# CircuitClockHandLayout.net
KiCad netlist of a schematic drawn in EAGLE
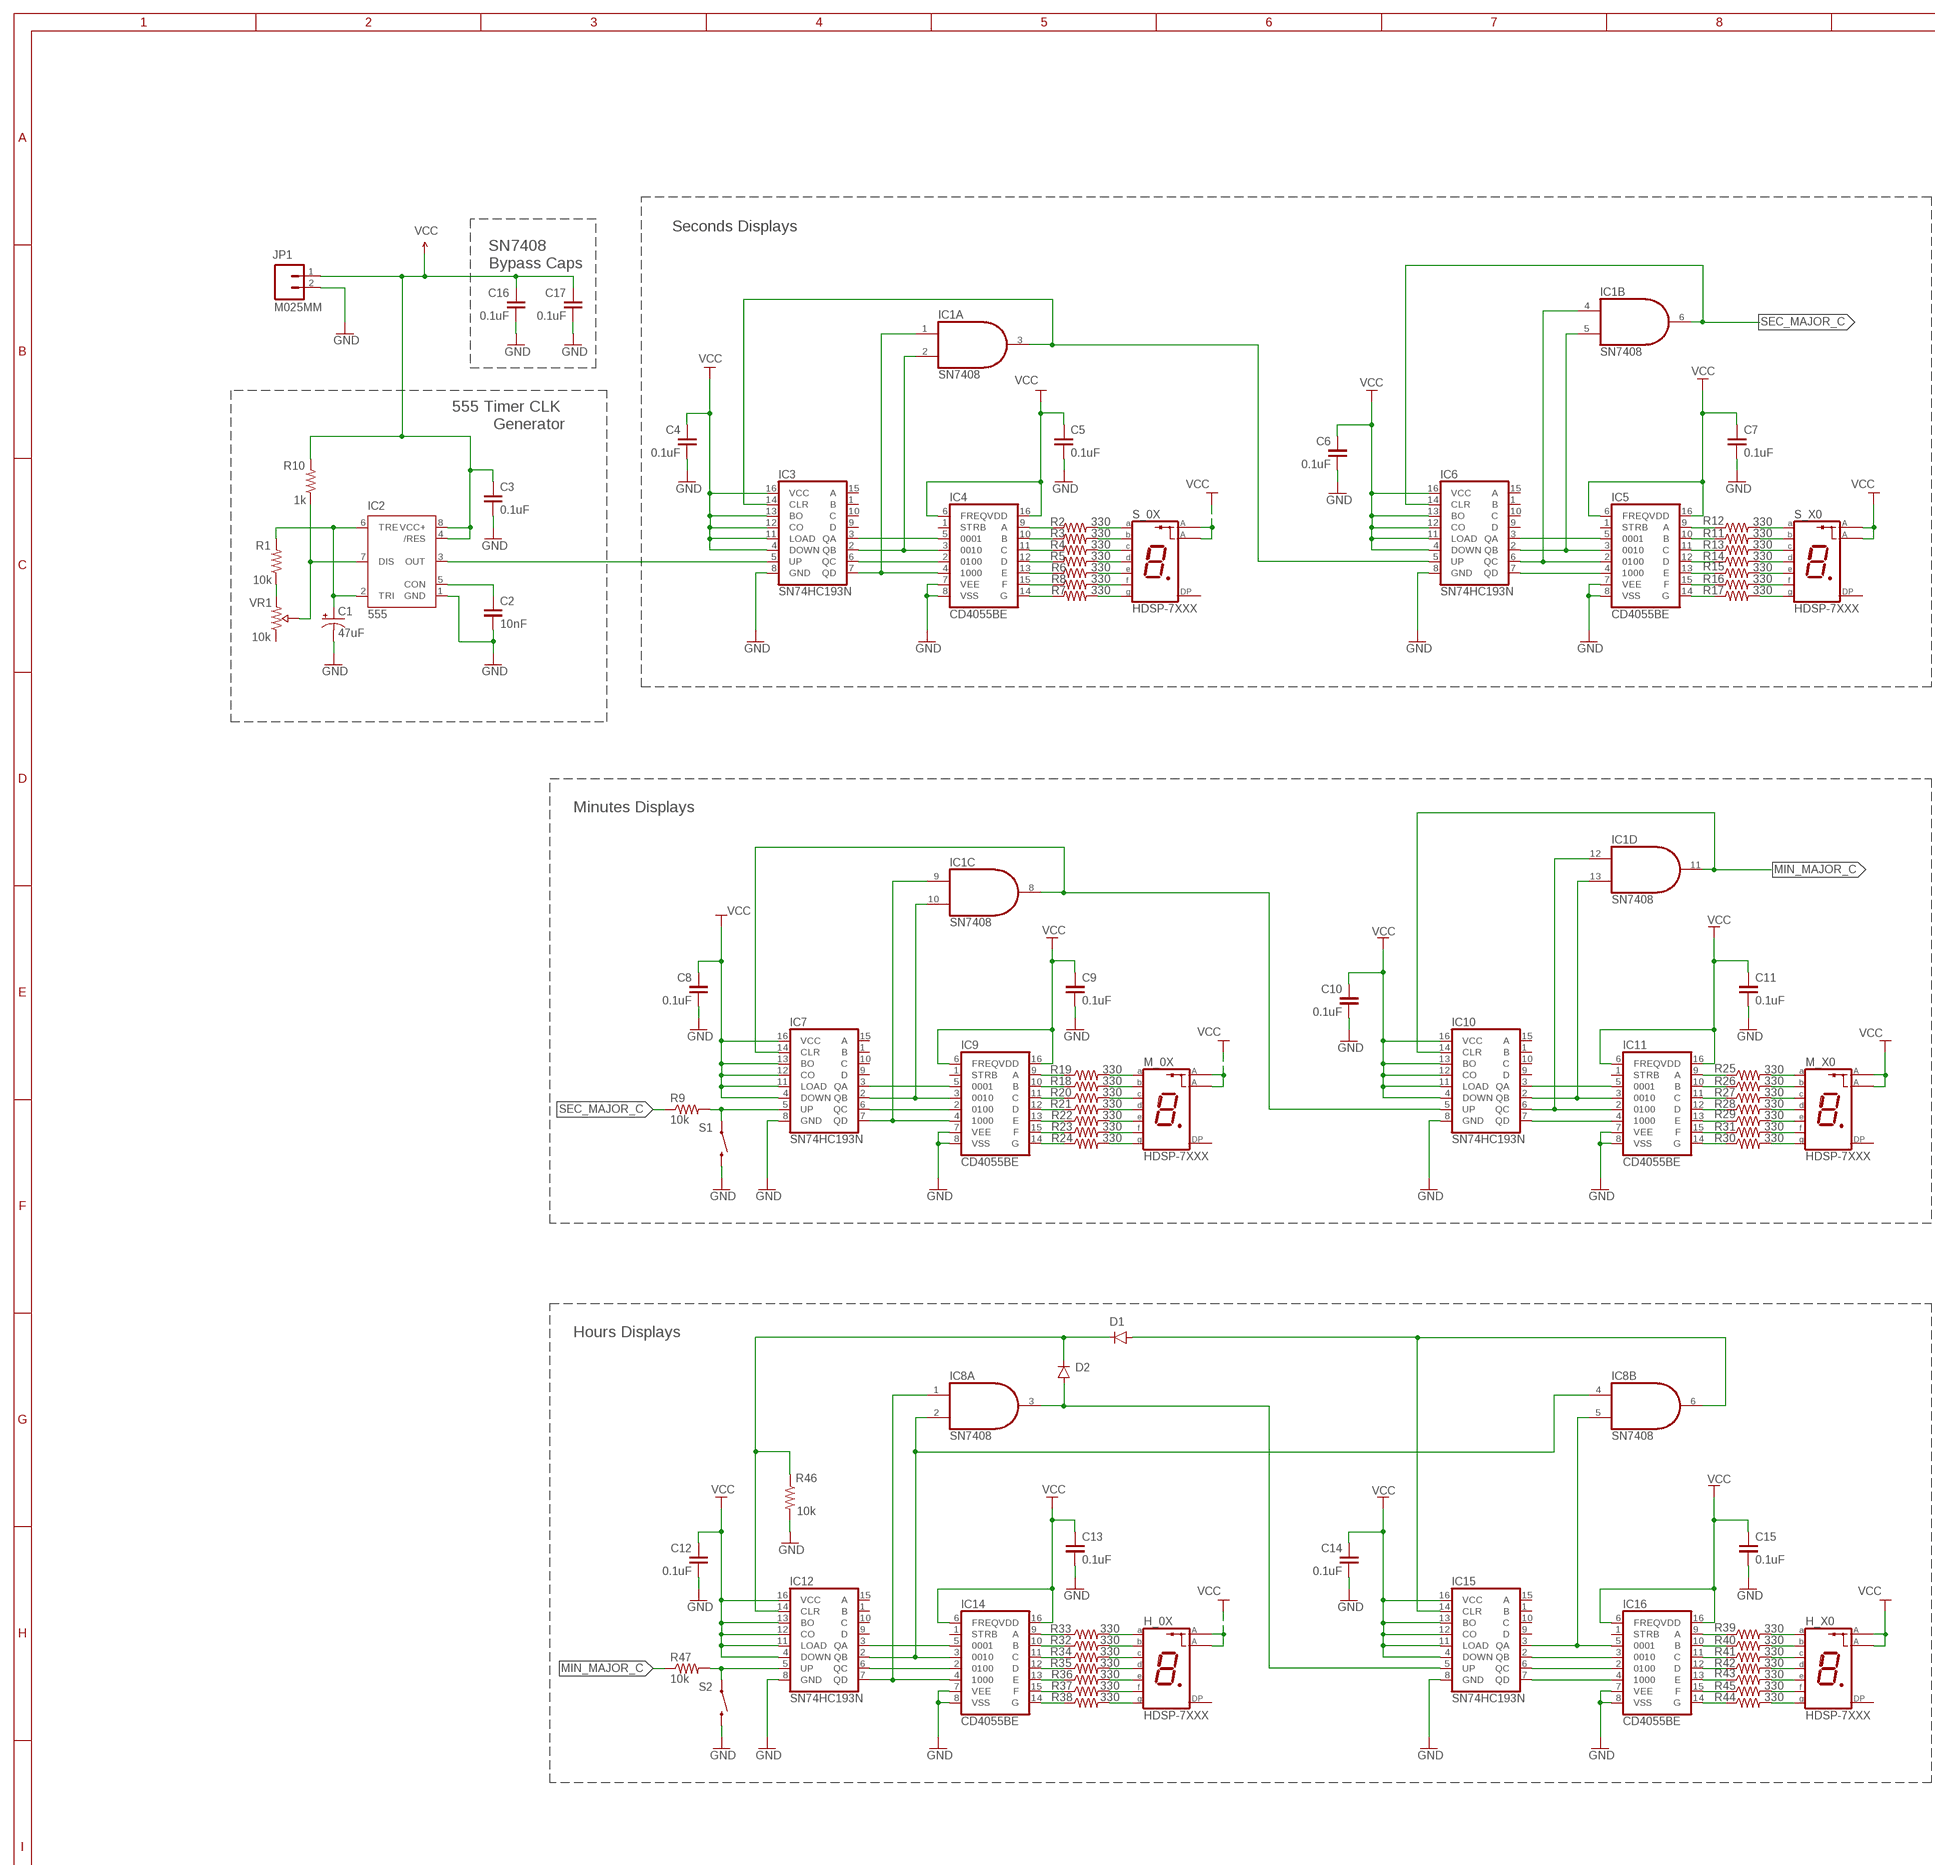
[diagram p0: schematic, sheet 1, part 1 of 2]
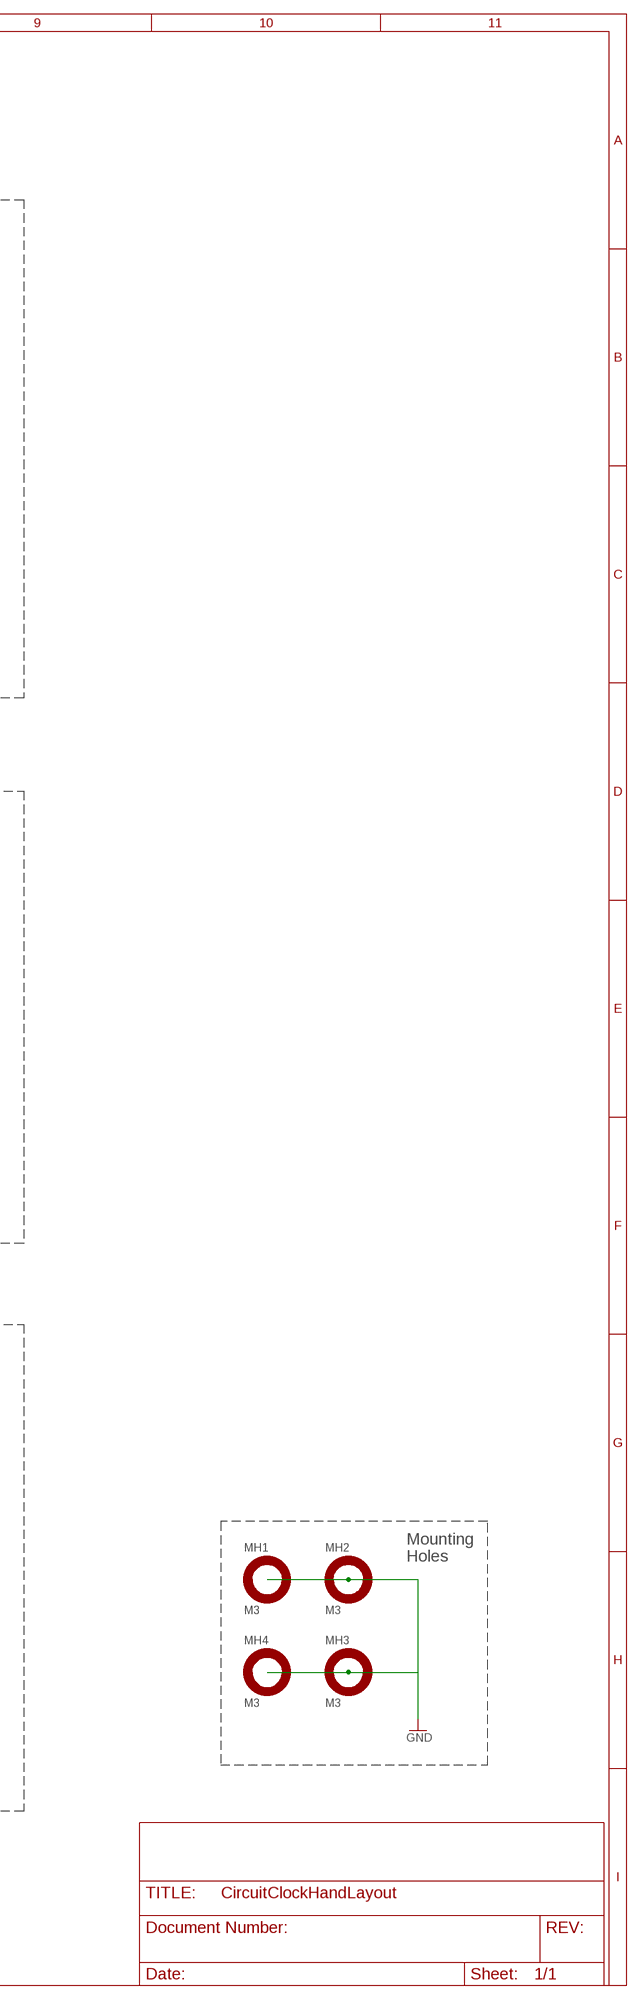
[diagram p1: schematic, sheet 1, part 2 of 2]

(export (version "E")
  (design (tool "Eeschema 10.0.6"))
  (components
    (comp (ref "C1")
      (value "47uF")
      (footprint "eagle-import:2.0MM_LEAD-5.0MM_DIA")
      (libsource (lib "eagle-import") (part "RADIAL_POL2.0MM_LEAD-5.0MM_DIA"))
    )
    (comp (ref "C2")
      (value "10nF")
      (footprint "eagle-import:2.54MM_LEAD")
      (libsource (lib "eagle-import") (part "NON_POL_2.5MM"))
    )
    (comp (ref "C3")
      (value "0.1uF")
      (footprint "eagle-import:2.54MM_LEAD")
      (libsource (lib "eagle-import") (part "NON_POL_2.5MM"))
    )
    (comp (ref "C4")
      (value "0.1uF")
      (footprint "eagle-import:2.54MM_LEAD")
      (libsource (lib "eagle-import") (part "NON_POL_2.5MM"))
    )
    (comp (ref "C5")
      (value "0.1uF")
      (footprint "eagle-import:2.54MM_LEAD")
      (libsource (lib "eagle-import") (part "NON_POL_2.5MM"))
    )
    (comp (ref "C6")
      (value "0.1uF")
      (footprint "eagle-import:2.54MM_LEAD")
      (libsource (lib "eagle-import") (part "NON_POL_2.5MM"))
    )
    (comp (ref "C7")
      (value "0.1uF")
      (footprint "eagle-import:2.54MM_LEAD")
      (libsource (lib "eagle-import") (part "NON_POL_2.5MM"))
    )
    (comp (ref "C8")
      (value "0.1uF")
      (footprint "eagle-import:2.54MM_LEAD")
      (libsource (lib "eagle-import") (part "NON_POL_2.5MM"))
    )
    (comp (ref "C9")
      (value "0.1uF")
      (footprint "eagle-import:2.54MM_LEAD")
      (libsource (lib "eagle-import") (part "NON_POL_2.5MM"))
    )
    (comp (ref "C10")
      (value "0.1uF")
      (footprint "eagle-import:2.54MM_LEAD")
      (libsource (lib "eagle-import") (part "NON_POL_2.5MM"))
    )
    (comp (ref "C11")
      (value "0.1uF")
      (footprint "eagle-import:2.54MM_LEAD")
      (libsource (lib "eagle-import") (part "NON_POL_2.5MM"))
    )
    (comp (ref "C12")
      (value "0.1uF")
      (footprint "eagle-import:2.54MM_LEAD")
      (libsource (lib "eagle-import") (part "NON_POL_2.5MM"))
    )
    (comp (ref "C13")
      (value "0.1uF")
      (footprint "eagle-import:2.54MM_LEAD")
      (libsource (lib "eagle-import") (part "NON_POL_2.5MM"))
    )
    (comp (ref "C14")
      (value "0.1uF")
      (footprint "eagle-import:2.54MM_LEAD")
      (libsource (lib "eagle-import") (part "NON_POL_2.5MM"))
    )
    (comp (ref "C15")
      (value "0.1uF")
      (footprint "eagle-import:2.54MM_LEAD")
      (libsource (lib "eagle-import") (part "NON_POL_2.5MM"))
    )
    (comp (ref "C16")
      (value "0.1uF")
      (footprint "eagle-import:2.54MM_LEAD")
      (libsource (lib "eagle-import") (part "NON_POL_2.5MM"))
    )
    (comp (ref "C17")
      (value "0.1uF")
      (footprint "eagle-import:2.54MM_LEAD")
      (libsource (lib "eagle-import") (part "NON_POL_2.5MM"))
    )
    (comp (ref "D1")
      (value "THROUGH_HOLE_DO-35")
      (footprint "eagle-import:DO35-10")
      (libsource (lib "eagle-import") (part "THROUGH_HOLE_DO-35"))
    )
    (comp (ref "D2")
      (value "THROUGH_HOLE_DO-35")
      (footprint "eagle-import:DO35-10")
      (libsource (lib "eagle-import") (part "THROUGH_HOLE_DO-35"))
    )
    (comp (ref "H_0X")
      (value "HDSP-7XXX")
      (footprint "eagle-import:HDSP-7XXX")
      (libsource (lib "eagle-import") (part "HDSP-7XXX"))
    )
    (comp (ref "H_X0")
      (value "HDSP-7XXX")
      (footprint "eagle-import:HDSP-7XXX")
      (libsource (lib "eagle-import") (part "HDSP-7XXX"))
    )
    (comp (ref "IC1")
      (value "SN7408")
      (footprint "eagle-import:DIL14")
      (libsource (lib "eagle-import") (part "7408NS"))
    )
    (comp (ref "IC2")
      (value "555")
      (footprint "eagle-import:DIP08-KIT")
      (libsource (lib "eagle-import") (part "555KIT"))
    )
    (comp (ref "IC3")
      (value "SN74HC193N")
      (footprint "eagle-import:DIL16")
      (libsource (lib "eagle-import") (part "SN74HC193N"))
    )
    (comp (ref "IC4")
      (value "CD4055BE")
      (footprint "eagle-import:DIL16")
      (libsource (lib "eagle-import") (part "CD4055BE"))
    )
    (comp (ref "IC5")
      (value "CD4055BE")
      (footprint "eagle-import:DIL16")
      (libsource (lib "eagle-import") (part "CD4055BE"))
    )
    (comp (ref "IC6")
      (value "SN74HC193N")
      (footprint "eagle-import:DIL16")
      (libsource (lib "eagle-import") (part "SN74HC193N"))
    )
    (comp (ref "IC7")
      (value "SN74HC193N")
      (footprint "eagle-import:DIL16")
      (libsource (lib "eagle-import") (part "SN74HC193N"))
    )
    (comp (ref "IC8")
      (value "SN7408")
      (footprint "eagle-import:DIL14")
      (libsource (lib "eagle-import") (part "7408NS"))
    )
    (comp (ref "IC9")
      (value "CD4055BE")
      (footprint "eagle-import:DIL16")
      (libsource (lib "eagle-import") (part "CD4055BE"))
    )
    (comp (ref "IC10")
      (value "SN74HC193N")
      (footprint "eagle-import:DIL16")
      (libsource (lib "eagle-import") (part "SN74HC193N"))
    )
    (comp (ref "IC11")
      (value "CD4055BE")
      (footprint "eagle-import:DIL16")
      (libsource (lib "eagle-import") (part "CD4055BE"))
    )
    (comp (ref "IC12")
      (value "SN74HC193N")
      (footprint "eagle-import:DIL16")
      (libsource (lib "eagle-import") (part "SN74HC193N"))
    )
    (comp (ref "IC14")
      (value "CD4055BE")
      (footprint "eagle-import:DIL16")
      (libsource (lib "eagle-import") (part "CD4055BE"))
    )
    (comp (ref "IC15")
      (value "SN74HC193N")
      (footprint "eagle-import:DIL16")
      (libsource (lib "eagle-import") (part "SN74HC193N"))
    )
    (comp (ref "IC16")
      (value "CD4055BE")
      (footprint "eagle-import:DIL16")
      (libsource (lib "eagle-import") (part "CD4055BE"))
    )
    (comp (ref "JP1")
      (value "M025MM")
      (footprint "eagle-import:SCREWTERMINAL-5MM-2")
      (libsource (lib "eagle-import") (part "M025MM"))
    )
    (comp (ref "MH1")
      (value "M3")
      (footprint "eagle-import:M3")
      (libsource (lib "eagle-import") (part "MOUNT_HOLEM3"))
    )
    (comp (ref "MH2")
      (value "M3")
      (footprint "eagle-import:M3")
      (libsource (lib "eagle-import") (part "MOUNT_HOLEM3"))
    )
    (comp (ref "MH3")
      (value "M3")
      (footprint "eagle-import:M3")
      (libsource (lib "eagle-import") (part "MOUNT_HOLEM3"))
    )
    (comp (ref "MH4")
      (value "M3")
      (footprint "eagle-import:M3")
      (libsource (lib "eagle-import") (part "MOUNT_HOLEM3"))
    )
    (comp (ref "M_0X")
      (value "HDSP-7XXX")
      (footprint "eagle-import:HDSP-7XXX")
      (libsource (lib "eagle-import") (part "HDSP-7XXX"))
    )
    (comp (ref "M_X0")
      (value "HDSP-7XXX")
      (footprint "eagle-import:HDSP-7XXX")
      (libsource (lib "eagle-import") (part "HDSP-7XXX"))
    )
    (comp (ref "R1")
      (value "10k")
      (footprint "eagle-import:1_4W_0.3")
      (libsource (lib "eagle-import") (part "THROUGH_HOLE_1/4W_0.3"))
    )
    (comp (ref "R2")
      (value "330")
      (footprint "eagle-import:1_4W_0.3")
      (libsource (lib "eagle-import") (part "THROUGH_HOLE_1/4W_0.3"))
    )
    (comp (ref "R3")
      (value "330")
      (footprint "eagle-import:1_4W_0.3")
      (libsource (lib "eagle-import") (part "THROUGH_HOLE_1/4W_0.3"))
    )
    (comp (ref "R4")
      (value "330")
      (footprint "eagle-import:1_4W_0.3")
      (libsource (lib "eagle-import") (part "THROUGH_HOLE_1/4W_0.3"))
    )
    (comp (ref "R5")
      (value "330")
      (footprint "eagle-import:1_4W_0.3")
      (libsource (lib "eagle-import") (part "THROUGH_HOLE_1/4W_0.3"))
    )
    (comp (ref "R6")
      (value "330")
      (footprint "eagle-import:1_4W_0.3")
      (libsource (lib "eagle-import") (part "THROUGH_HOLE_1/4W_0.3"))
    )
    (comp (ref "R7")
      (value "330")
      (footprint "eagle-import:1_4W_0.3")
      (libsource (lib "eagle-import") (part "THROUGH_HOLE_1/4W_0.3"))
    )
    (comp (ref "R8")
      (value "330")
      (footprint "eagle-import:1_4W_0.3")
      (libsource (lib "eagle-import") (part "THROUGH_HOLE_1/4W_0.3"))
    )
    (comp (ref "R9")
      (value "10k")
      (footprint "eagle-import:1_4W_0.3")
      (libsource (lib "eagle-import") (part "THROUGH_HOLE_1/4W_0.3"))
    )
    (comp (ref "R10")
      (value "1k")
      (footprint "eagle-import:1_4W_0.3")
      (libsource (lib "eagle-import") (part "THROUGH_HOLE_1/4W_0.3"))
    )
    (comp (ref "R11")
      (value "330")
      (footprint "eagle-import:1_4W_0.3")
      (libsource (lib "eagle-import") (part "THROUGH_HOLE_1/4W_0.3"))
    )
    (comp (ref "R12")
      (value "330")
      (footprint "eagle-import:1_4W_0.3")
      (libsource (lib "eagle-import") (part "THROUGH_HOLE_1/4W_0.3"))
    )
    (comp (ref "R13")
      (value "330")
      (footprint "eagle-import:1_4W_0.3")
      (libsource (lib "eagle-import") (part "THROUGH_HOLE_1/4W_0.3"))
    )
    (comp (ref "R14")
      (value "330")
      (footprint "eagle-import:1_4W_0.3")
      (libsource (lib "eagle-import") (part "THROUGH_HOLE_1/4W_0.3"))
    )
    (comp (ref "R15")
      (value "330")
      (footprint "eagle-import:1_4W_0.3")
      (libsource (lib "eagle-import") (part "THROUGH_HOLE_1/4W_0.3"))
    )
    (comp (ref "R16")
      (value "330")
      (footprint "eagle-import:1_4W_0.3")
      (libsource (lib "eagle-import") (part "THROUGH_HOLE_1/4W_0.3"))
    )
    (comp (ref "R17")
      (value "330")
      (footprint "eagle-import:1_4W_0.3")
      (libsource (lib "eagle-import") (part "THROUGH_HOLE_1/4W_0.3"))
    )
    (comp (ref "R18")
      (value "330")
      (footprint "eagle-import:1_4W_0.3")
      (libsource (lib "eagle-import") (part "THROUGH_HOLE_1/4W_0.3"))
    )
    (comp (ref "R19")
      (value "330")
      (footprint "eagle-import:1_4W_0.3")
      (libsource (lib "eagle-import") (part "THROUGH_HOLE_1/4W_0.3"))
    )
    (comp (ref "R20")
      (value "330")
      (footprint "eagle-import:1_4W_0.3")
      (libsource (lib "eagle-import") (part "THROUGH_HOLE_1/4W_0.3"))
    )
    (comp (ref "R21")
      (value "330")
      (footprint "eagle-import:1_4W_0.3")
      (libsource (lib "eagle-import") (part "THROUGH_HOLE_1/4W_0.3"))
    )
    (comp (ref "R22")
      (value "330")
      (footprint "eagle-import:1_4W_0.3")
      (libsource (lib "eagle-import") (part "THROUGH_HOLE_1/4W_0.3"))
    )
    (comp (ref "R23")
      (value "330")
      (footprint "eagle-import:1_4W_0.3")
      (libsource (lib "eagle-import") (part "THROUGH_HOLE_1/4W_0.3"))
    )
    (comp (ref "R24")
      (value "330")
      (footprint "eagle-import:1_4W_0.3")
      (libsource (lib "eagle-import") (part "THROUGH_HOLE_1/4W_0.3"))
    )
    (comp (ref "R25")
      (value "330")
      (footprint "eagle-import:1_4W_0.3")
      (libsource (lib "eagle-import") (part "THROUGH_HOLE_1/4W_0.3"))
    )
    (comp (ref "R26")
      (value "330")
      (footprint "eagle-import:1_4W_0.3")
      (libsource (lib "eagle-import") (part "THROUGH_HOLE_1/4W_0.3"))
    )
    (comp (ref "R27")
      (value "330")
      (footprint "eagle-import:1_4W_0.3")
      (libsource (lib "eagle-import") (part "THROUGH_HOLE_1/4W_0.3"))
    )
    (comp (ref "R28")
      (value "330")
      (footprint "eagle-import:1_4W_0.3")
      (libsource (lib "eagle-import") (part "THROUGH_HOLE_1/4W_0.3"))
    )
    (comp (ref "R29")
      (value "330")
      (footprint "eagle-import:1_4W_0.3")
      (libsource (lib "eagle-import") (part "THROUGH_HOLE_1/4W_0.3"))
    )
    (comp (ref "R30")
      (value "330")
      (footprint "eagle-import:1_4W_0.3")
      (libsource (lib "eagle-import") (part "THROUGH_HOLE_1/4W_0.3"))
    )
    (comp (ref "R31")
      (value "330")
      (footprint "eagle-import:1_4W_0.3")
      (libsource (lib "eagle-import") (part "THROUGH_HOLE_1/4W_0.3"))
    )
    (comp (ref "R32")
      (value "330")
      (footprint "eagle-import:1_4W_0.3")
      (libsource (lib "eagle-import") (part "THROUGH_HOLE_1/4W_0.3"))
    )
    (comp (ref "R33")
      (value "330")
      (footprint "eagle-import:1_4W_0.3")
      (libsource (lib "eagle-import") (part "THROUGH_HOLE_1/4W_0.3"))
    )
    (comp (ref "R34")
      (value "330")
      (footprint "eagle-import:1_4W_0.3")
      (libsource (lib "eagle-import") (part "THROUGH_HOLE_1/4W_0.3"))
    )
    (comp (ref "R35")
      (value "330")
      (footprint "eagle-import:1_4W_0.3")
      (libsource (lib "eagle-import") (part "THROUGH_HOLE_1/4W_0.3"))
    )
    (comp (ref "R36")
      (value "330")
      (footprint "eagle-import:1_4W_0.3")
      (libsource (lib "eagle-import") (part "THROUGH_HOLE_1/4W_0.3"))
    )
    (comp (ref "R37")
      (value "330")
      (footprint "eagle-import:1_4W_0.3")
      (libsource (lib "eagle-import") (part "THROUGH_HOLE_1/4W_0.3"))
    )
    (comp (ref "R38")
      (value "330")
      (footprint "eagle-import:1_4W_0.3")
      (libsource (lib "eagle-import") (part "THROUGH_HOLE_1/4W_0.3"))
    )
    (comp (ref "R39")
      (value "330")
      (footprint "eagle-import:1_4W_0.3")
      (libsource (lib "eagle-import") (part "THROUGH_HOLE_1/4W_0.3"))
    )
    (comp (ref "R40")
      (value "330")
      (footprint "eagle-import:1_4W_0.3")
      (libsource (lib "eagle-import") (part "THROUGH_HOLE_1/4W_0.3"))
    )
    (comp (ref "R41")
      (value "330")
      (footprint "eagle-import:1_4W_0.3")
      (libsource (lib "eagle-import") (part "THROUGH_HOLE_1/4W_0.3"))
    )
    (comp (ref "R42")
      (value "330")
      (footprint "eagle-import:1_4W_0.3")
      (libsource (lib "eagle-import") (part "THROUGH_HOLE_1/4W_0.3"))
    )
    (comp (ref "R43")
      (value "330")
      (footprint "eagle-import:1_4W_0.3")
      (libsource (lib "eagle-import") (part "THROUGH_HOLE_1/4W_0.3"))
    )
    (comp (ref "R44")
      (value "330")
      (footprint "eagle-import:1_4W_0.3")
      (libsource (lib "eagle-import") (part "THROUGH_HOLE_1/4W_0.3"))
    )
    (comp (ref "R45")
      (value "330")
      (footprint "eagle-import:1_4W_0.3")
      (libsource (lib "eagle-import") (part "THROUGH_HOLE_1/4W_0.3"))
    )
    (comp (ref "R46")
      (value "10k")
      (footprint "eagle-import:1_4W_0.3")
      (libsource (lib "eagle-import") (part "THROUGH_HOLE_1/4W_0.3"))
    )
    (comp (ref "R47")
      (value "10k")
      (footprint "eagle-import:1_4W_0.3")
      (libsource (lib "eagle-import") (part "THROUGH_HOLE_1/4W_0.3"))
    )
    (comp (ref "S1")
      (value "SWITCH-MOMENTARY-2PTH")
      (footprint "eagle-import:TACTILE-PTH")
      (libsource (lib "eagle-import") (part "SWITCH-MOMENTARY-2PTH"))
    )
    (comp (ref "S2")
      (value "SWITCH-MOMENTARY-2PTH")
      (footprint "eagle-import:TACTILE-PTH")
      (libsource (lib "eagle-import") (part "SWITCH-MOMENTARY-2PTH"))
    )
    (comp (ref "S_0X")
      (value "HDSP-7XXX")
      (footprint "eagle-import:HDSP-7XXX")
      (libsource (lib "eagle-import") (part "HDSP-7XXX"))
    )
    (comp (ref "S_X0")
      (value "HDSP-7XXX")
      (footprint "eagle-import:HDSP-7XXX")
      (libsource (lib "eagle-import") (part "HDSP-7XXX"))
    )
    (comp (ref "VR1")
      (value "10k")
      (footprint "eagle-import:3296")
      (libsource (lib "eagle-import") (part "TRIM_POTS_BOURNS_3296"))
    )
  )
  (nets
    (net (code "1") (name "GND") (class "Default")
      (node (ref "C1") (pin "-") (pinfunction "-_-") (pintype "passive"))
      (node (ref "C10") (pin "2") (pinfunction "2_2") (pintype "passive"))
      (node (ref "C11") (pin "2") (pinfunction "2_2") (pintype "passive"))
      (node (ref "C12") (pin "2") (pinfunction "2_2") (pintype "passive"))
      (node (ref "C13") (pin "2") (pinfunction "2_2") (pintype "passive"))
      (node (ref "C14") (pin "2") (pinfunction "2_2") (pintype "passive"))
      (node (ref "C15") (pin "2") (pinfunction "2_2") (pintype "passive"))
      (node (ref "C16") (pin "2") (pinfunction "2_2") (pintype "passive"))
      (node (ref "C17") (pin "2") (pinfunction "2_2") (pintype "passive"))
      (node (ref "C2") (pin "2") (pinfunction "2_2") (pintype "passive"))
      (node (ref "C3") (pin "2") (pinfunction "2_2") (pintype "passive"))
      (node (ref "C4") (pin "2") (pinfunction "2_2") (pintype "passive"))
      (node (ref "C5") (pin "2") (pinfunction "2_2") (pintype "passive"))
      (node (ref "C6") (pin "2") (pinfunction "2_2") (pintype "passive"))
      (node (ref "C7") (pin "2") (pinfunction "2_2") (pintype "passive"))
      (node (ref "C8") (pin "2") (pinfunction "2_2") (pintype "passive"))
      (node (ref "C9") (pin "2") (pinfunction "2_2") (pintype "passive"))
      (node (ref "IC10") (pin "8") (pinfunction "GND_8") (pintype "power_in"))
      (node (ref "IC11") (pin "7") (pinfunction "VEE_7") (pintype "bidirectional"))
      (node (ref "IC11") (pin "8") (pinfunction "VSS_8") (pintype "power_in"))
      (node (ref "IC12") (pin "8") (pinfunction "GND_8") (pintype "power_in"))
      (node (ref "IC14") (pin "7") (pinfunction "VEE_7") (pintype "bidirectional"))
      (node (ref "IC14") (pin "8") (pinfunction "VSS_8") (pintype "power_in"))
      (node (ref "IC15") (pin "8") (pinfunction "GND_8") (pintype "power_in"))
      (node (ref "IC16") (pin "7") (pinfunction "VEE_7") (pintype "bidirectional"))
      (node (ref "IC16") (pin "8") (pinfunction "VSS_8") (pintype "power_in"))
      (node (ref "IC2") (pin "1") (pinfunction "GND_1") (pintype "power_in"))
      (node (ref "IC3") (pin "8") (pinfunction "GND_8") (pintype "power_in"))
      (node (ref "IC4") (pin "7") (pinfunction "VEE_7") (pintype "bidirectional"))
      (node (ref "IC4") (pin "8") (pinfunction "VSS_8") (pintype "power_in"))
      (node (ref "IC5") (pin "7") (pinfunction "VEE_7") (pintype "bidirectional"))
      (node (ref "IC5") (pin "8") (pinfunction "VSS_8") (pintype "power_in"))
      (node (ref "IC6") (pin "8") (pinfunction "GND_8") (pintype "power_in"))
      (node (ref "IC7") (pin "8") (pinfunction "GND_8") (pintype "power_in"))
      (node (ref "IC9") (pin "7") (pinfunction "VEE_7") (pintype "bidirectional"))
      (node (ref "IC9") (pin "8") (pinfunction "VSS_8") (pintype "power_in"))
      (node (ref "JP1") (pin "2") (pinfunction "2_2") (pintype "passive"))
      (node (ref "MH1") (pin "P$1") (pinfunction "P$1_P$1") (pintype "bidirectional"))
      (node (ref "MH2") (pin "P$1") (pinfunction "P$1_P$1") (pintype "bidirectional"))
      (node (ref "MH3") (pin "P$1") (pinfunction "P$1_P$1") (pintype "bidirectional"))
      (node (ref "MH4") (pin "P$1") (pinfunction "P$1_P$1") (pintype "bidirectional"))
      (node (ref "R46") (pin "P$2") (pinfunction "2_P$2") (pintype "passive"))
      (node (ref "S1") (pin "3") (pinfunction "2_3") (pintype "passive"))
      (node (ref "S2") (pin "3") (pinfunction "2_3") (pintype "passive"))
    )
    (net (code "2") (name "MIN_MAJOR_C") (class "Default")
      (node (ref "IC1") (pin "11") (pinfunction "O_11") (pintype "output"))
      (node (ref "IC10") (pin "14") (pinfunction "CLR_14") (pintype "bidirectional"))
      (node (ref "R47") (pin "P$1") (pinfunction "1_P$1") (pintype "passive"))
    )
    (net (code "3") (name "Net-(H_0X-B)") (class "Default")
      (node (ref "H_0X") (pin "P$9") (pinfunction "B_P$9") (pintype "passive"))
      (node (ref "R32") (pin "P$2") (pinfunction "2_P$2") (pintype "passive"))
    )
    (net (code "4") (name "Net-(H_0X-C)") (class "Default")
      (node (ref "H_0X") (pin "P$8") (pinfunction "C_P$8") (pintype "passive"))
      (node (ref "R34") (pin "P$2") (pinfunction "2_P$2") (pintype "passive"))
    )
    (net (code "5") (name "Net-(H_0X-D)") (class "Default")
      (node (ref "H_0X") (pin "P$5") (pinfunction "D_P$5") (pintype "passive"))
      (node (ref "R35") (pin "P$2") (pinfunction "2_P$2") (pintype "passive"))
    )
    (net (code "6") (name "Net-(H_0X-E)") (class "Default")
      (node (ref "H_0X") (pin "P$4") (pinfunction "E_P$4") (pintype "passive"))
      (node (ref "R36") (pin "P$2") (pinfunction "2_P$2") (pintype "passive"))
    )
    (net (code "7") (name "Net-(H_0X-F)") (class "Default")
      (node (ref "H_0X") (pin "P$2") (pinfunction "F_P$2") (pintype "passive"))
      (node (ref "R37") (pin "P$2") (pinfunction "2_P$2") (pintype "passive"))
    )
    (net (code "8") (name "Net-(H_0X-G)") (class "Default")
      (node (ref "H_0X") (pin "P$3") (pinfunction "G_P$3") (pintype "passive"))
      (node (ref "R38") (pin "P$2") (pinfunction "2_P$2") (pintype "passive"))
    )
    (net (code "9") (name "Net-(H_X0-B)") (class "Default")
      (node (ref "H_X0") (pin "P$9") (pinfunction "B_P$9") (pintype "passive"))
      (node (ref "R40") (pin "P$2") (pinfunction "2_P$2") (pintype "passive"))
    )
    (net (code "10") (name "Net-(H_X0-C)") (class "Default")
      (node (ref "H_X0") (pin "P$8") (pinfunction "C_P$8") (pintype "passive"))
      (node (ref "R41") (pin "P$2") (pinfunction "2_P$2") (pintype "passive"))
    )
    (net (code "11") (name "Net-(H_X0-D)") (class "Default")
      (node (ref "H_X0") (pin "P$5") (pinfunction "D_P$5") (pintype "passive"))
      (node (ref "R42") (pin "P$2") (pinfunction "2_P$2") (pintype "passive"))
    )
    (net (code "12") (name "Net-(H_X0-E)") (class "Default")
      (node (ref "H_X0") (pin "P$4") (pinfunction "E_P$4") (pintype "passive"))
      (node (ref "R43") (pin "P$2") (pinfunction "2_P$2") (pintype "passive"))
    )
    (net (code "13") (name "Net-(H_X0-F)") (class "Default")
      (node (ref "H_X0") (pin "P$2") (pinfunction "F_P$2") (pintype "passive"))
      (node (ref "R45") (pin "P$2") (pinfunction "2_P$2") (pintype "passive"))
    )
    (net (code "14") (name "Net-(H_X0-G)") (class "Default")
      (node (ref "H_X0") (pin "P$3") (pinfunction "G_P$3") (pintype "passive"))
      (node (ref "R44") (pin "P$2") (pinfunction "2_P$2") (pintype "passive"))
    )
    (net (code "15") (name "Net-(IC1A-I0)") (class "Default")
      (node (ref "IC1") (pin "1") (pinfunction "I0_1") (pintype "input"))
      (node (ref "IC3") (pin "7") (pinfunction "QD_7") (pintype "bidirectional"))
      (node (ref "IC4") (pin "4") (pinfunction "1000_4") (pintype "bidirectional"))
    )
    (net (code "16") (name "Net-(IC1A-I1)") (class "Default")
      (node (ref "IC1") (pin "2") (pinfunction "I1_2") (pintype "input"))
      (node (ref "IC3") (pin "2") (pinfunction "QB_2") (pintype "bidirectional"))
      (node (ref "IC4") (pin "3") (pinfunction "0010_3") (pintype "input"))
    )
    (net (code "17") (name "Net-(IC1A-O)") (class "Default")
      (node (ref "IC1") (pin "3") (pinfunction "O_3") (pintype "output"))
      (node (ref "IC3") (pin "14") (pinfunction "CLR_14") (pintype "bidirectional"))
      (node (ref "IC6") (pin "5") (pinfunction "UP_5") (pintype "bidirectional"))
    )
    (net (code "18") (name "Net-(IC1B-I0)") (class "Default")
      (node (ref "IC1") (pin "4") (pinfunction "I0_4") (pintype "input"))
      (node (ref "IC5") (pin "2") (pinfunction "0100_2") (pintype "input"))
      (node (ref "IC6") (pin "6") (pinfunction "QC_6") (pintype "bidirectional"))
    )
    (net (code "19") (name "Net-(IC1B-I1)") (class "Default")
      (node (ref "IC1") (pin "5") (pinfunction "I1_5") (pintype "input"))
      (node (ref "IC5") (pin "3") (pinfunction "0010_3") (pintype "input"))
      (node (ref "IC6") (pin "2") (pinfunction "QB_2") (pintype "bidirectional"))
    )
    (net (code "20") (name "Net-(IC1C-I0)") (class "Default")
      (node (ref "IC1") (pin "9") (pinfunction "I0_9") (pintype "input"))
      (node (ref "IC7") (pin "7") (pinfunction "QD_7") (pintype "bidirectional"))
      (node (ref "IC9") (pin "4") (pinfunction "1000_4") (pintype "bidirectional"))
    )
    (net (code "21") (name "Net-(IC1C-I1)") (class "Default")
      (node (ref "IC1") (pin "10") (pinfunction "I1_10") (pintype "input"))
      (node (ref "IC7") (pin "2") (pinfunction "QB_2") (pintype "bidirectional"))
      (node (ref "IC9") (pin "3") (pinfunction "0010_3") (pintype "input"))
    )
    (net (code "22") (name "Net-(IC2-CON)") (class "Default")
      (node (ref "C2") (pin "1") (pinfunction "1_1") (pintype "passive"))
      (node (ref "IC2") (pin "5") (pinfunction "CON_5") (pintype "input"))
    )
    (net (code "23") (name "Net-(IC2-DIS)") (class "Default")
      (node (ref "IC2") (pin "7") (pinfunction "DIS_7") (pintype "input"))
      (node (ref "R10") (pin "P$1") (pinfunction "1_P$1") (pintype "passive"))
      (node (ref "VR1") (pin "2") (pinfunction "S_2") (pintype "passive"))
    )
    (net (code "24") (name "Net-(IC2-OUT)") (class "Default")
      (node (ref "IC2") (pin "3") (pinfunction "OUT_3") (pintype "output"))
      (node (ref "IC3") (pin "5") (pinfunction "UP_5") (pintype "bidirectional"))
    )
    (net (code "25") (name "Net-(IC2-TRE)") (class "Default")
      (node (ref "C1") (pin "+") (pinfunction "+_+") (pintype "passive"))
      (node (ref "IC2") (pin "2") (pinfunction "TRI_2") (pintype "input"))
      (node (ref "IC2") (pin "6") (pinfunction "TRE_6") (pintype "input"))
      (node (ref "R1") (pin "P$2") (pinfunction "2_P$2") (pintype "passive"))
    )
    (net (code "26") (name "Net-(IC3-QA)") (class "Default")
      (node (ref "IC3") (pin "3") (pinfunction "QA_3") (pintype "bidirectional"))
      (node (ref "IC4") (pin "5") (pinfunction "0001_5") (pintype "input"))
    )
    (net (code "27") (name "Net-(IC3-QC)") (class "Default")
      (node (ref "IC3") (pin "6") (pinfunction "QC_6") (pintype "bidirectional"))
      (node (ref "IC4") (pin "2") (pinfunction "0100_2") (pintype "input"))
    )
    (net (code "28") (name "Net-(IC4-A)") (class "Default")
      (node (ref "IC4") (pin "9") (pinfunction "A_9") (pintype "bidirectional"))
      (node (ref "R2") (pin "P$1") (pinfunction "1_P$1") (pintype "passive"))
    )
    (net (code "29") (name "Net-(IC4-B)") (class "Default")
      (node (ref "IC4") (pin "10") (pinfunction "B_10") (pintype "bidirectional"))
      (node (ref "R3") (pin "P$1") (pinfunction "1_P$1") (pintype "passive"))
    )
    (net (code "30") (name "Net-(IC4-C)") (class "Default")
      (node (ref "IC4") (pin "11") (pinfunction "C_11") (pintype "bidirectional"))
      (node (ref "R4") (pin "P$1") (pinfunction "1_P$1") (pintype "passive"))
    )
    (net (code "31") (name "Net-(IC4-D)") (class "Default")
      (node (ref "IC4") (pin "12") (pinfunction "D_12") (pintype "bidirectional"))
      (node (ref "R5") (pin "P$1") (pinfunction "1_P$1") (pintype "passive"))
    )
    (net (code "32") (name "Net-(IC4-E)") (class "Default")
      (node (ref "IC4") (pin "13") (pinfunction "E_13") (pintype "bidirectional"))
      (node (ref "R6") (pin "P$1") (pinfunction "1_P$1") (pintype "passive"))
    )
    (net (code "33") (name "Net-(IC4-F)") (class "Default")
      (node (ref "IC4") (pin "15") (pinfunction "F_15") (pintype "bidirectional"))
      (node (ref "R8") (pin "P$1") (pinfunction "1_P$1") (pintype "passive"))
    )
    (net (code "34") (name "Net-(IC4-G)") (class "Default")
      (node (ref "IC4") (pin "14") (pinfunction "G_14") (pintype "bidirectional"))
      (node (ref "R7") (pin "P$1") (pinfunction "1_P$1") (pintype "passive"))
    )
    (net (code "35") (name "Net-(IC5-0001)") (class "Default")
      (node (ref "IC5") (pin "5") (pinfunction "0001_5") (pintype "input"))
      (node (ref "IC6") (pin "3") (pinfunction "QA_3") (pintype "bidirectional"))
    )
    (net (code "36") (name "Net-(IC5-1000)") (class "Default")
      (node (ref "IC5") (pin "4") (pinfunction "1000_4") (pintype "bidirectional"))
      (node (ref "IC6") (pin "7") (pinfunction "QD_7") (pintype "bidirectional"))
    )
    (net (code "37") (name "Net-(IC5-A)") (class "Default")
      (node (ref "IC5") (pin "9") (pinfunction "A_9") (pintype "bidirectional"))
      (node (ref "R12") (pin "P$1") (pinfunction "1_P$1") (pintype "passive"))
    )
    (net (code "38") (name "Net-(IC5-B)") (class "Default")
      (node (ref "IC5") (pin "10") (pinfunction "B_10") (pintype "bidirectional"))
      (node (ref "R11") (pin "P$1") (pinfunction "1_P$1") (pintype "passive"))
    )
    (net (code "39") (name "Net-(IC5-C)") (class "Default")
      (node (ref "IC5") (pin "11") (pinfunction "C_11") (pintype "bidirectional"))
      (node (ref "R13") (pin "P$1") (pinfunction "1_P$1") (pintype "passive"))
    )
    (net (code "40") (name "Net-(IC5-D)") (class "Default")
      (node (ref "IC5") (pin "12") (pinfunction "D_12") (pintype "bidirectional"))
      (node (ref "R14") (pin "P$1") (pinfunction "1_P$1") (pintype "passive"))
    )
    (net (code "41") (name "Net-(IC5-E)") (class "Default")
      (node (ref "IC5") (pin "13") (pinfunction "E_13") (pintype "bidirectional"))
      (node (ref "R15") (pin "P$1") (pinfunction "1_P$1") (pintype "passive"))
    )
    (net (code "42") (name "Net-(IC5-F)") (class "Default")
      (node (ref "IC5") (pin "15") (pinfunction "F_15") (pintype "bidirectional"))
      (node (ref "R16") (pin "P$1") (pinfunction "1_P$1") (pintype "passive"))
    )
    (net (code "43") (name "Net-(IC5-G)") (class "Default")
      (node (ref "IC5") (pin "14") (pinfunction "G_14") (pintype "bidirectional"))
      (node (ref "R17") (pin "P$1") (pinfunction "1_P$1") (pintype "passive"))
    )
    (net (code "44") (name "Net-(IC7-QA)") (class "Default")
      (node (ref "IC7") (pin "3") (pinfunction "QA_3") (pintype "bidirectional"))
      (node (ref "IC9") (pin "5") (pinfunction "0001_5") (pintype "input"))
    )
    (net (code "45") (name "Net-(IC7-QC)") (class "Default")
      (node (ref "IC7") (pin "6") (pinfunction "QC_6") (pintype "bidirectional"))
      (node (ref "IC9") (pin "2") (pinfunction "0100_2") (pintype "input"))
    )
    (net (code "46") (name "Net-(IC7-UP)") (class "Default")
      (node (ref "IC7") (pin "5") (pinfunction "UP_5") (pintype "bidirectional"))
      (node (ref "R9") (pin "P$2") (pinfunction "2_P$2") (pintype "passive"))
      (node (ref "S1") (pin "1") (pinfunction "1_1") (pintype "passive"))
    )
    (net (code "47") (name "Net-(IC9-A)") (class "Default")
      (node (ref "IC9") (pin "9") (pinfunction "A_9") (pintype "bidirectional"))
      (node (ref "R19") (pin "P$1") (pinfunction "1_P$1") (pintype "passive"))
    )
    (net (code "48") (name "Net-(IC9-B)") (class "Default")
      (node (ref "IC9") (pin "10") (pinfunction "B_10") (pintype "bidirectional"))
      (node (ref "R18") (pin "P$1") (pinfunction "1_P$1") (pintype "passive"))
    )
    (net (code "49") (name "Net-(IC9-C)") (class "Default")
      (node (ref "IC9") (pin "11") (pinfunction "C_11") (pintype "bidirectional"))
      (node (ref "R20") (pin "P$1") (pinfunction "1_P$1") (pintype "passive"))
    )
    (net (code "50") (name "Net-(IC9-D)") (class "Default")
      (node (ref "IC9") (pin "12") (pinfunction "D_12") (pintype "bidirectional"))
      (node (ref "R21") (pin "P$1") (pinfunction "1_P$1") (pintype "passive"))
    )
    (net (code "51") (name "Net-(IC9-E)") (class "Default")
      (node (ref "IC9") (pin "13") (pinfunction "E_13") (pintype "bidirectional"))
      (node (ref "R22") (pin "P$1") (pinfunction "1_P$1") (pintype "passive"))
    )
    (net (code "52") (name "Net-(IC9-F)") (class "Default")
      (node (ref "IC9") (pin "15") (pinfunction "F_15") (pintype "bidirectional"))
      (node (ref "R23") (pin "P$1") (pinfunction "1_P$1") (pintype "passive"))
    )
    (net (code "53") (name "Net-(IC9-G)") (class "Default")
      (node (ref "IC9") (pin "14") (pinfunction "G_14") (pintype "bidirectional"))
      (node (ref "R24") (pin "P$1") (pinfunction "1_P$1") (pintype "passive"))
    )
    (net (code "54") (name "Net-(IC10-QA)") (class "Default")
      (node (ref "IC10") (pin "3") (pinfunction "QA_3") (pintype "bidirectional"))
      (node (ref "IC11") (pin "5") (pinfunction "0001_5") (pintype "input"))
    )
    (net (code "55") (name "Net-(IC10-QB)") (class "Default")
      (node (ref "IC1") (pin "13") (pinfunction "I1_13") (pintype "input"))
      (node (ref "IC10") (pin "2") (pinfunction "QB_2") (pintype "bidirectional"))
      (node (ref "IC11") (pin "3") (pinfunction "0010_3") (pintype "input"))
    )
    (net (code "56") (name "Net-(IC10-QC)") (class "Default")
      (node (ref "IC1") (pin "12") (pinfunction "I0_12") (pintype "input"))
      (node (ref "IC10") (pin "6") (pinfunction "QC_6") (pintype "bidirectional"))
      (node (ref "IC11") (pin "2") (pinfunction "0100_2") (pintype "input"))
    )
    (net (code "57") (name "Net-(IC10-QD)") (class "Default")
      (node (ref "IC10") (pin "7") (pinfunction "QD_7") (pintype "bidirectional"))
      (node (ref "IC11") (pin "4") (pinfunction "1000_4") (pintype "bidirectional"))
    )
    (net (code "58") (name "Net-(IC10-UP)") (class "Default")
      (node (ref "IC1") (pin "8") (pinfunction "O_8") (pintype "output"))
      (node (ref "IC10") (pin "5") (pinfunction "UP_5") (pintype "bidirectional"))
      (node (ref "IC7") (pin "14") (pinfunction "CLR_14") (pintype "bidirectional"))
    )
    (net (code "59") (name "Net-(IC11-A)") (class "Default")
      (node (ref "IC11") (pin "9") (pinfunction "A_9") (pintype "bidirectional"))
      (node (ref "R25") (pin "P$1") (pinfunction "1_P$1") (pintype "passive"))
    )
    (net (code "60") (name "Net-(IC11-B)") (class "Default")
      (node (ref "IC11") (pin "10") (pinfunction "B_10") (pintype "bidirectional"))
      (node (ref "R26") (pin "P$1") (pinfunction "1_P$1") (pintype "passive"))
    )
    (net (code "61") (name "Net-(IC11-C)") (class "Default")
      (node (ref "IC11") (pin "11") (pinfunction "C_11") (pintype "bidirectional"))
      (node (ref "R27") (pin "P$1") (pinfunction "1_P$1") (pintype "passive"))
    )
    (net (code "62") (name "Net-(IC11-D)") (class "Default")
      (node (ref "IC11") (pin "12") (pinfunction "D_12") (pintype "bidirectional"))
      (node (ref "R28") (pin "P$1") (pinfunction "1_P$1") (pintype "passive"))
    )
    (net (code "63") (name "Net-(IC11-E)") (class "Default")
      (node (ref "IC11") (pin "13") (pinfunction "E_13") (pintype "bidirectional"))
      (node (ref "R29") (pin "P$1") (pinfunction "1_P$1") (pintype "passive"))
    )
    (net (code "64") (name "Net-(IC11-F)") (class "Default")
      (node (ref "IC11") (pin "15") (pinfunction "F_15") (pintype "bidirectional"))
      (node (ref "R31") (pin "P$1") (pinfunction "1_P$1") (pintype "passive"))
    )
    (net (code "65") (name "Net-(IC11-G)") (class "Default")
      (node (ref "IC11") (pin "14") (pinfunction "G_14") (pintype "bidirectional"))
      (node (ref "R30") (pin "P$1") (pinfunction "1_P$1") (pintype "passive"))
    )
    (net (code "66") (name "Net-(IC12-CLR)") (class "Default")
      (node (ref "D1") (pin "C") (pinfunction "C_C") (pintype "passive"))
      (node (ref "D2") (pin "C") (pinfunction "C_C") (pintype "passive"))
      (node (ref "IC12") (pin "14") (pinfunction "CLR_14") (pintype "bidirectional"))
      (node (ref "R46") (pin "P$1") (pinfunction "1_P$1") (pintype "passive"))
    )
    (net (code "67") (name "Net-(IC12-QA)") (class "Default")
      (node (ref "IC12") (pin "3") (pinfunction "QA_3") (pintype "bidirectional"))
      (node (ref "IC14") (pin "5") (pinfunction "0001_5") (pintype "input"))
    )
    (net (code "68") (name "Net-(IC12-QB)") (class "Default")
      (node (ref "IC12") (pin "2") (pinfunction "QB_2") (pintype "bidirectional"))
      (node (ref "IC14") (pin "3") (pinfunction "0010_3") (pintype "input"))
      (node (ref "IC8") (pin "2") (pinfunction "I1_2") (pintype "input"))
      (node (ref "IC8") (pin "4") (pinfunction "I0_4") (pintype "input"))
    )
    (net (code "69") (name "Net-(IC12-QC)") (class "Default")
      (node (ref "IC12") (pin "6") (pinfunction "QC_6") (pintype "bidirectional"))
      (node (ref "IC14") (pin "2") (pinfunction "0100_2") (pintype "input"))
    )
    (net (code "70") (name "Net-(IC12-QD)") (class "Default")
      (node (ref "IC12") (pin "7") (pinfunction "QD_7") (pintype "bidirectional"))
      (node (ref "IC14") (pin "4") (pinfunction "1000_4") (pintype "bidirectional"))
      (node (ref "IC8") (pin "1") (pinfunction "I0_1") (pintype "input"))
    )
    (net (code "71") (name "Net-(IC12-UP)") (class "Default")
      (node (ref "IC12") (pin "5") (pinfunction "UP_5") (pintype "bidirectional"))
      (node (ref "R47") (pin "P$2") (pinfunction "2_P$2") (pintype "passive"))
      (node (ref "S2") (pin "1") (pinfunction "1_1") (pintype "passive"))
    )
    (net (code "72") (name "Net-(IC14-A)") (class "Default")
      (node (ref "IC14") (pin "9") (pinfunction "A_9") (pintype "bidirectional"))
      (node (ref "R33") (pin "P$1") (pinfunction "1_P$1") (pintype "passive"))
    )
    (net (code "73") (name "Net-(IC14-B)") (class "Default")
      (node (ref "IC14") (pin "10") (pinfunction "B_10") (pintype "bidirectional"))
      (node (ref "R32") (pin "P$1") (pinfunction "1_P$1") (pintype "passive"))
    )
    (net (code "74") (name "Net-(IC14-C)") (class "Default")
      (node (ref "IC14") (pin "11") (pinfunction "C_11") (pintype "bidirectional"))
      (node (ref "R34") (pin "P$1") (pinfunction "1_P$1") (pintype "passive"))
    )
    (net (code "75") (name "Net-(IC14-D)") (class "Default")
      (node (ref "IC14") (pin "12") (pinfunction "D_12") (pintype "bidirectional"))
      (node (ref "R35") (pin "P$1") (pinfunction "1_P$1") (pintype "passive"))
    )
    (net (code "76") (name "Net-(IC14-E)") (class "Default")
      (node (ref "IC14") (pin "13") (pinfunction "E_13") (pintype "bidirectional"))
      (node (ref "R36") (pin "P$1") (pinfunction "1_P$1") (pintype "passive"))
    )
    (net (code "77") (name "Net-(IC14-F)") (class "Default")
      (node (ref "IC14") (pin "15") (pinfunction "F_15") (pintype "bidirectional"))
      (node (ref "R37") (pin "P$1") (pinfunction "1_P$1") (pintype "passive"))
    )
    (net (code "78") (name "Net-(IC14-G)") (class "Default")
      (node (ref "IC14") (pin "14") (pinfunction "G_14") (pintype "bidirectional"))
      (node (ref "R38") (pin "P$1") (pinfunction "1_P$1") (pintype "passive"))
    )
    (net (code "79") (name "Net-(IC15-CLR)") (class "Default")
      (node (ref "D1") (pin "A") (pinfunction "A_A") (pintype "passive"))
      (node (ref "IC15") (pin "14") (pinfunction "CLR_14") (pintype "bidirectional"))
      (node (ref "IC8") (pin "6") (pinfunction "O_6") (pintype "output"))
    )
    (net (code "80") (name "Net-(IC15-QA)") (class "Default")
      (node (ref "IC15") (pin "3") (pinfunction "QA_3") (pintype "bidirectional"))
      (node (ref "IC16") (pin "5") (pinfunction "0001_5") (pintype "input"))
      (node (ref "IC8") (pin "5") (pinfunction "I1_5") (pintype "input"))
    )
    (net (code "81") (name "Net-(IC15-QB)") (class "Default")
      (node (ref "IC15") (pin "2") (pinfunction "QB_2") (pintype "bidirectional"))
      (node (ref "IC16") (pin "3") (pinfunction "0010_3") (pintype "input"))
    )
    (net (code "82") (name "Net-(IC15-QC)") (class "Default")
      (node (ref "IC15") (pin "6") (pinfunction "QC_6") (pintype "bidirectional"))
      (node (ref "IC16") (pin "2") (pinfunction "0100_2") (pintype "input"))
    )
    (net (code "83") (name "Net-(IC15-QD)") (class "Default")
      (node (ref "IC15") (pin "7") (pinfunction "QD_7") (pintype "bidirectional"))
      (node (ref "IC16") (pin "4") (pinfunction "1000_4") (pintype "bidirectional"))
    )
    (net (code "84") (name "Net-(IC15-UP)") (class "Default")
      (node (ref "D2") (pin "A") (pinfunction "A_A") (pintype "passive"))
      (node (ref "IC15") (pin "5") (pinfunction "UP_5") (pintype "bidirectional"))
      (node (ref "IC8") (pin "3") (pinfunction "O_3") (pintype "output"))
    )
    (net (code "85") (name "Net-(IC16-A)") (class "Default")
      (node (ref "IC16") (pin "9") (pinfunction "A_9") (pintype "bidirectional"))
      (node (ref "R39") (pin "P$1") (pinfunction "1_P$1") (pintype "passive"))
    )
    (net (code "86") (name "Net-(IC16-B)") (class "Default")
      (node (ref "IC16") (pin "10") (pinfunction "B_10") (pintype "bidirectional"))
      (node (ref "R40") (pin "P$1") (pinfunction "1_P$1") (pintype "passive"))
    )
    (net (code "87") (name "Net-(IC16-C)") (class "Default")
      (node (ref "IC16") (pin "11") (pinfunction "C_11") (pintype "bidirectional"))
      (node (ref "R41") (pin "P$1") (pinfunction "1_P$1") (pintype "passive"))
    )
    (net (code "88") (name "Net-(IC16-D)") (class "Default")
      (node (ref "IC16") (pin "12") (pinfunction "D_12") (pintype "bidirectional"))
      (node (ref "R42") (pin "P$1") (pinfunction "1_P$1") (pintype "passive"))
    )
    (net (code "89") (name "Net-(IC16-E)") (class "Default")
      (node (ref "IC16") (pin "13") (pinfunction "E_13") (pintype "bidirectional"))
      (node (ref "R43") (pin "P$1") (pinfunction "1_P$1") (pintype "passive"))
    )
    (net (code "90") (name "Net-(IC16-F)") (class "Default")
      (node (ref "IC16") (pin "15") (pinfunction "F_15") (pintype "bidirectional"))
      (node (ref "R45") (pin "P$1") (pinfunction "1_P$1") (pintype "passive"))
    )
    (net (code "91") (name "Net-(IC16-G)") (class "Default")
      (node (ref "IC16") (pin "14") (pinfunction "G_14") (pintype "bidirectional"))
      (node (ref "R44") (pin "P$1") (pinfunction "1_P$1") (pintype "passive"))
    )
    (net (code "92") (name "Net-(M_0X-B)") (class "Default")
      (node (ref "M_0X") (pin "P$9") (pinfunction "B_P$9") (pintype "passive"))
      (node (ref "R18") (pin "P$2") (pinfunction "2_P$2") (pintype "passive"))
    )
    (net (code "93") (name "Net-(M_0X-C)") (class "Default")
      (node (ref "M_0X") (pin "P$8") (pinfunction "C_P$8") (pintype "passive"))
      (node (ref "R20") (pin "P$2") (pinfunction "2_P$2") (pintype "passive"))
    )
    (net (code "94") (name "Net-(M_0X-D)") (class "Default")
      (node (ref "M_0X") (pin "P$5") (pinfunction "D_P$5") (pintype "passive"))
      (node (ref "R21") (pin "P$2") (pinfunction "2_P$2") (pintype "passive"))
    )
    (net (code "95") (name "Net-(M_0X-E)") (class "Default")
      (node (ref "M_0X") (pin "P$4") (pinfunction "E_P$4") (pintype "passive"))
      (node (ref "R22") (pin "P$2") (pinfunction "2_P$2") (pintype "passive"))
    )
    (net (code "96") (name "Net-(M_0X-F)") (class "Default")
      (node (ref "M_0X") (pin "P$2") (pinfunction "F_P$2") (pintype "passive"))
      (node (ref "R23") (pin "P$2") (pinfunction "2_P$2") (pintype "passive"))
    )
    (net (code "97") (name "Net-(M_0X-G)") (class "Default")
      (node (ref "M_0X") (pin "P$3") (pinfunction "G_P$3") (pintype "passive"))
      (node (ref "R24") (pin "P$2") (pinfunction "2_P$2") (pintype "passive"))
    )
    (net (code "98") (name "Net-(M_X0-B)") (class "Default")
      (node (ref "M_X0") (pin "P$9") (pinfunction "B_P$9") (pintype "passive"))
      (node (ref "R26") (pin "P$2") (pinfunction "2_P$2") (pintype "passive"))
    )
    (net (code "99") (name "Net-(M_X0-C)") (class "Default")
      (node (ref "M_X0") (pin "P$8") (pinfunction "C_P$8") (pintype "passive"))
      (node (ref "R27") (pin "P$2") (pinfunction "2_P$2") (pintype "passive"))
    )
    (net (code "100") (name "Net-(M_X0-D)") (class "Default")
      (node (ref "M_X0") (pin "P$5") (pinfunction "D_P$5") (pintype "passive"))
      (node (ref "R28") (pin "P$2") (pinfunction "2_P$2") (pintype "passive"))
    )
    (net (code "101") (name "Net-(M_X0-E)") (class "Default")
      (node (ref "M_X0") (pin "P$4") (pinfunction "E_P$4") (pintype "passive"))
      (node (ref "R29") (pin "P$2") (pinfunction "2_P$2") (pintype "passive"))
    )
    (net (code "102") (name "Net-(M_X0-F)") (class "Default")
      (node (ref "M_X0") (pin "P$2") (pinfunction "F_P$2") (pintype "passive"))
      (node (ref "R31") (pin "P$2") (pinfunction "2_P$2") (pintype "passive"))
    )
    (net (code "103") (name "Net-(M_X0-G)") (class "Default")
      (node (ref "M_X0") (pin "P$3") (pinfunction "G_P$3") (pintype "passive"))
      (node (ref "R30") (pin "P$2") (pinfunction "2_P$2") (pintype "passive"))
    )
    (net (code "104") (name "Net-(R1-1)") (class "Default")
      (node (ref "R1") (pin "P$1") (pinfunction "1_P$1") (pintype "passive"))
      (node (ref "VR1") (pin "3") (pinfunction "E_3") (pintype "passive"))
    )
    (net (code "105") (name "Net-(R2-2)") (class "Default")
      (node (ref "R2") (pin "P$2") (pinfunction "2_P$2") (pintype "passive"))
      (node (ref "S_0X") (pin "P$10") (pinfunction "A_P$10") (pintype "passive"))
    )
    (net (code "106") (name "Net-(R3-2)") (class "Default")
      (node (ref "R3") (pin "P$2") (pinfunction "2_P$2") (pintype "passive"))
      (node (ref "S_0X") (pin "P$9") (pinfunction "B_P$9") (pintype "passive"))
    )
    (net (code "107") (name "Net-(R4-2)") (class "Default")
      (node (ref "R4") (pin "P$2") (pinfunction "2_P$2") (pintype "passive"))
      (node (ref "S_0X") (pin "P$8") (pinfunction "C_P$8") (pintype "passive"))
    )
    (net (code "108") (name "Net-(R5-2)") (class "Default")
      (node (ref "R5") (pin "P$2") (pinfunction "2_P$2") (pintype "passive"))
      (node (ref "S_0X") (pin "P$5") (pinfunction "D_P$5") (pintype "passive"))
    )
    (net (code "109") (name "Net-(R6-2)") (class "Default")
      (node (ref "R6") (pin "P$2") (pinfunction "2_P$2") (pintype "passive"))
      (node (ref "S_0X") (pin "P$4") (pinfunction "E_P$4") (pintype "passive"))
    )
    (net (code "110") (name "Net-(R7-2)") (class "Default")
      (node (ref "R7") (pin "P$2") (pinfunction "2_P$2") (pintype "passive"))
      (node (ref "S_0X") (pin "P$3") (pinfunction "G_P$3") (pintype "passive"))
    )
    (net (code "111") (name "Net-(R8-2)") (class "Default")
      (node (ref "R8") (pin "P$2") (pinfunction "2_P$2") (pintype "passive"))
      (node (ref "S_0X") (pin "P$2") (pinfunction "F_P$2") (pintype "passive"))
    )
    (net (code "112") (name "Net-(R11-2)") (class "Default")
      (node (ref "R11") (pin "P$2") (pinfunction "2_P$2") (pintype "passive"))
      (node (ref "S_X0") (pin "P$9") (pinfunction "B_P$9") (pintype "passive"))
    )
    (net (code "113") (name "Net-(R12-2)") (class "Default")
      (node (ref "R12") (pin "P$2") (pinfunction "2_P$2") (pintype "passive"))
      (node (ref "S_X0") (pin "P$10") (pinfunction "A_P$10") (pintype "passive"))
    )
    (net (code "114") (name "Net-(R13-2)") (class "Default")
      (node (ref "R13") (pin "P$2") (pinfunction "2_P$2") (pintype "passive"))
      (node (ref "S_X0") (pin "P$8") (pinfunction "C_P$8") (pintype "passive"))
    )
    (net (code "115") (name "Net-(R14-2)") (class "Default")
      (node (ref "R14") (pin "P$2") (pinfunction "2_P$2") (pintype "passive"))
      (node (ref "S_X0") (pin "P$5") (pinfunction "D_P$5") (pintype "passive"))
    )
    (net (code "116") (name "Net-(R15-2)") (class "Default")
      (node (ref "R15") (pin "P$2") (pinfunction "2_P$2") (pintype "passive"))
      (node (ref "S_X0") (pin "P$4") (pinfunction "E_P$4") (pintype "passive"))
    )
    (net (code "117") (name "Net-(R16-2)") (class "Default")
      (node (ref "R16") (pin "P$2") (pinfunction "2_P$2") (pintype "passive"))
      (node (ref "S_X0") (pin "P$2") (pinfunction "F_P$2") (pintype "passive"))
    )
    (net (code "118") (name "Net-(R17-2)") (class "Default")
      (node (ref "R17") (pin "P$2") (pinfunction "2_P$2") (pintype "passive"))
      (node (ref "S_X0") (pin "P$3") (pinfunction "G_P$3") (pintype "passive"))
    )
    (net (code "119") (name "Net-(R19-2)") (class "Default")
      (node (ref "M_0X") (pin "P$10") (pinfunction "A_P$10") (pintype "passive"))
      (node (ref "R19") (pin "P$2") (pinfunction "2_P$2") (pintype "passive"))
    )
    (net (code "120") (name "Net-(R25-2)") (class "Default")
      (node (ref "M_X0") (pin "P$10") (pinfunction "A_P$10") (pintype "passive"))
      (node (ref "R25") (pin "P$2") (pinfunction "2_P$2") (pintype "passive"))
    )
    (net (code "121") (name "Net-(R33-2)") (class "Default")
      (node (ref "H_0X") (pin "P$10") (pinfunction "A_P$10") (pintype "passive"))
      (node (ref "R33") (pin "P$2") (pinfunction "2_P$2") (pintype "passive"))
    )
    (net (code "122") (name "Net-(R39-2)") (class "Default")
      (node (ref "H_X0") (pin "P$10") (pinfunction "A_P$10") (pintype "passive"))
      (node (ref "R39") (pin "P$2") (pinfunction "2_P$2") (pintype "passive"))
    )
    (net (code "123") (name "SEC_MAJOR_C") (class "Default")
      (node (ref "IC1") (pin "6") (pinfunction "O_6") (pintype "output"))
      (node (ref "IC6") (pin "14") (pinfunction "CLR_14") (pintype "bidirectional"))
      (node (ref "R9") (pin "P$1") (pinfunction "1_P$1") (pintype "passive"))
    )
    (net (code "124") (name "SINK_UNDEFINED") (class "Default")
      (node (ref "C10") (pin "1") (pinfunction "1_1") (pintype "passive"))
      (node (ref "C11") (pin "1") (pinfunction "1_1") (pintype "passive"))
      (node (ref "C12") (pin "1") (pinfunction "1_1") (pintype "passive"))
      (node (ref "C13") (pin "1") (pinfunction "1_1") (pintype "passive"))
      (node (ref "C14") (pin "1") (pinfunction "1_1") (pintype "passive"))
      (node (ref "C15") (pin "1") (pinfunction "1_1") (pintype "passive"))
      (node (ref "C16") (pin "1") (pinfunction "1_1") (pintype "passive"))
      (node (ref "C17") (pin "1") (pinfunction "1_1") (pintype "passive"))
      (node (ref "C3") (pin "1") (pinfunction "1_1") (pintype "passive"))
      (node (ref "C4") (pin "1") (pinfunction "1_1") (pintype "passive"))
      (node (ref "C5") (pin "1") (pinfunction "1_1") (pintype "passive"))
      (node (ref "C6") (pin "1") (pinfunction "1_1") (pintype "passive"))
      (node (ref "C7") (pin "1") (pinfunction "1_1") (pintype "passive"))
      (node (ref "C8") (pin "1") (pinfunction "1_1") (pintype "passive"))
      (node (ref "C9") (pin "1") (pinfunction "1_1") (pintype "passive"))
      (node (ref "H_0X") (pin "P$1") (pinfunction "A_P$1") (pintype "passive"))
      (node (ref "H_0X") (pin "P$6") (pinfunction "A_P$6") (pintype "passive"))
      (node (ref "H_X0") (pin "P$1") (pinfunction "A_P$1") (pintype "passive"))
      (node (ref "H_X0") (pin "P$6") (pinfunction "A_P$6") (pintype "passive"))
      (node (ref "IC10") (pin "11") (pinfunction "LOAD_11") (pintype "input"))
      (node (ref "IC10") (pin "12") (pinfunction "CO_12") (pintype "input"))
      (node (ref "IC10") (pin "13") (pinfunction "BO_13") (pintype "bidirectional"))
      (node (ref "IC10") (pin "16") (pinfunction "VCC_16") (pintype "power_in"))
      (node (ref "IC10") (pin "4") (pinfunction "DOWN_4") (pintype "input"))
      (node (ref "IC11") (pin "16") (pinfunction "VDD_16") (pintype "power_in"))
      (node (ref "IC11") (pin "6") (pinfunction "FREQ_6") (pintype "bidirectional"))
      (node (ref "IC12") (pin "11") (pinfunction "LOAD_11") (pintype "input"))
      (node (ref "IC12") (pin "12") (pinfunction "CO_12") (pintype "input"))
      (node (ref "IC12") (pin "13") (pinfunction "BO_13") (pintype "bidirectional"))
      (node (ref "IC12") (pin "16") (pinfunction "VCC_16") (pintype "power_in"))
      (node (ref "IC12") (pin "4") (pinfunction "DOWN_4") (pintype "input"))
      (node (ref "IC14") (pin "16") (pinfunction "VDD_16") (pintype "power_in"))
      (node (ref "IC14") (pin "6") (pinfunction "FREQ_6") (pintype "bidirectional"))
      (node (ref "IC15") (pin "11") (pinfunction "LOAD_11") (pintype "input"))
      (node (ref "IC15") (pin "12") (pinfunction "CO_12") (pintype "input"))
      (node (ref "IC15") (pin "13") (pinfunction "BO_13") (pintype "bidirectional"))
      (node (ref "IC15") (pin "16") (pinfunction "VCC_16") (pintype "power_in"))
      (node (ref "IC15") (pin "4") (pinfunction "DOWN_4") (pintype "input"))
      (node (ref "IC16") (pin "16") (pinfunction "VDD_16") (pintype "power_in"))
      (node (ref "IC16") (pin "6") (pinfunction "FREQ_6") (pintype "bidirectional"))
      (node (ref "IC2") (pin "4") (pinfunction "/RES_4") (pintype "input"))
      (node (ref "IC2") (pin "8") (pinfunction "VCC+_8") (pintype "power_in"))
      (node (ref "IC3") (pin "11") (pinfunction "LOAD_11") (pintype "input"))
      (node (ref "IC3") (pin "12") (pinfunction "CO_12") (pintype "input"))
      (node (ref "IC3") (pin "13") (pinfunction "BO_13") (pintype "bidirectional"))
      (node (ref "IC3") (pin "16") (pinfunction "VCC_16") (pintype "power_in"))
      (node (ref "IC3") (pin "4") (pinfunction "DOWN_4") (pintype "input"))
      (node (ref "IC4") (pin "16") (pinfunction "VDD_16") (pintype "power_in"))
      (node (ref "IC4") (pin "6") (pinfunction "FREQ_6") (pintype "bidirectional"))
      (node (ref "IC5") (pin "16") (pinfunction "VDD_16") (pintype "power_in"))
      (node (ref "IC5") (pin "6") (pinfunction "FREQ_6") (pintype "bidirectional"))
      (node (ref "IC6") (pin "11") (pinfunction "LOAD_11") (pintype "input"))
      (node (ref "IC6") (pin "12") (pinfunction "CO_12") (pintype "input"))
      (node (ref "IC6") (pin "13") (pinfunction "BO_13") (pintype "bidirectional"))
      (node (ref "IC6") (pin "16") (pinfunction "VCC_16") (pintype "power_in"))
      (node (ref "IC6") (pin "4") (pinfunction "DOWN_4") (pintype "input"))
      (node (ref "IC7") (pin "11") (pinfunction "LOAD_11") (pintype "input"))
      (node (ref "IC7") (pin "12") (pinfunction "CO_12") (pintype "input"))
      (node (ref "IC7") (pin "13") (pinfunction "BO_13") (pintype "bidirectional"))
      (node (ref "IC7") (pin "16") (pinfunction "VCC_16") (pintype "power_in"))
      (node (ref "IC7") (pin "4") (pinfunction "DOWN_4") (pintype "input"))
      (node (ref "IC9") (pin "16") (pinfunction "VDD_16") (pintype "power_in"))
      (node (ref "IC9") (pin "6") (pinfunction "FREQ_6") (pintype "bidirectional"))
      (node (ref "JP1") (pin "1") (pinfunction "1_1") (pintype "passive"))
      (node (ref "M_0X") (pin "P$1") (pinfunction "A_P$1") (pintype "passive"))
      (node (ref "M_0X") (pin "P$6") (pinfunction "A_P$6") (pintype "passive"))
      (node (ref "M_X0") (pin "P$1") (pinfunction "A_P$1") (pintype "passive"))
      (node (ref "M_X0") (pin "P$6") (pinfunction "A_P$6") (pintype "passive"))
      (node (ref "R10") (pin "P$2") (pinfunction "2_P$2") (pintype "passive"))
      (node (ref "S_0X") (pin "P$1") (pinfunction "A_P$1") (pintype "passive"))
      (node (ref "S_0X") (pin "P$6") (pinfunction "A_P$6") (pintype "passive"))
      (node (ref "S_X0") (pin "P$1") (pinfunction "A_P$1") (pintype "passive"))
      (node (ref "S_X0") (pin "P$6") (pinfunction "A_P$6") (pintype "passive"))
    )
    (net (code "125") (name "unconnected-(H_0X-DP-PadP$7)") (class "Default")
      (node (ref "H_0X") (pin "P$7") (pinfunction "DP_P$7") (pintype "passive"))
    )
    (net (code "126") (name "unconnected-(H_X0-DP-PadP$7)") (class "Default")
      (node (ref "H_X0") (pin "P$7") (pinfunction "DP_P$7") (pintype "passive"))
    )
    (net (code "127") (name "unconnected-(IC3-A-Pad15)") (class "Default")
      (node (ref "IC3") (pin "15") (pinfunction "A_15") (pintype "bidirectional"))
    )
    (net (code "128") (name "unconnected-(IC3-B-Pad1)") (class "Default")
      (node (ref "IC3") (pin "1") (pinfunction "B_1") (pintype "bidirectional"))
    )
    (net (code "129") (name "unconnected-(IC3-C-Pad10)") (class "Default")
      (node (ref "IC3") (pin "10") (pinfunction "C_10") (pintype "bidirectional"))
    )
    (net (code "130") (name "unconnected-(IC3-D-Pad9)") (class "Default")
      (node (ref "IC3") (pin "9") (pinfunction "D_9") (pintype "bidirectional"))
    )
    (net (code "131") (name "unconnected-(IC4-STRB-Pad1)") (class "Default")
      (node (ref "IC4") (pin "1") (pinfunction "STRB_1") (pintype "bidirectional"))
    )
    (net (code "132") (name "unconnected-(IC5-STRB-Pad1)") (class "Default")
      (node (ref "IC5") (pin "1") (pinfunction "STRB_1") (pintype "bidirectional"))
    )
    (net (code "133") (name "unconnected-(IC6-A-Pad15)") (class "Default")
      (node (ref "IC6") (pin "15") (pinfunction "A_15") (pintype "bidirectional"))
    )
    (net (code "134") (name "unconnected-(IC6-B-Pad1)") (class "Default")
      (node (ref "IC6") (pin "1") (pinfunction "B_1") (pintype "bidirectional"))
    )
    (net (code "135") (name "unconnected-(IC6-C-Pad10)") (class "Default")
      (node (ref "IC6") (pin "10") (pinfunction "C_10") (pintype "bidirectional"))
    )
    (net (code "136") (name "unconnected-(IC6-D-Pad9)") (class "Default")
      (node (ref "IC6") (pin "9") (pinfunction "D_9") (pintype "bidirectional"))
    )
    (net (code "137") (name "unconnected-(IC7-A-Pad15)") (class "Default")
      (node (ref "IC7") (pin "15") (pinfunction "A_15") (pintype "bidirectional"))
    )
    (net (code "138") (name "unconnected-(IC7-B-Pad1)") (class "Default")
      (node (ref "IC7") (pin "1") (pinfunction "B_1") (pintype "bidirectional"))
    )
    (net (code "139") (name "unconnected-(IC7-C-Pad10)") (class "Default")
      (node (ref "IC7") (pin "10") (pinfunction "C_10") (pintype "bidirectional"))
    )
    (net (code "140") (name "unconnected-(IC7-D-Pad9)") (class "Default")
      (node (ref "IC7") (pin "9") (pinfunction "D_9") (pintype "bidirectional"))
    )
    (net (code "141") (name "unconnected-(IC9-STRB-Pad1)") (class "Default")
      (node (ref "IC9") (pin "1") (pinfunction "STRB_1") (pintype "bidirectional"))
    )
    (net (code "142") (name "unconnected-(IC10-A-Pad15)") (class "Default")
      (node (ref "IC10") (pin "15") (pinfunction "A_15") (pintype "bidirectional"))
    )
    (net (code "143") (name "unconnected-(IC10-B-Pad1)") (class "Default")
      (node (ref "IC10") (pin "1") (pinfunction "B_1") (pintype "bidirectional"))
    )
    (net (code "144") (name "unconnected-(IC10-C-Pad10)") (class "Default")
      (node (ref "IC10") (pin "10") (pinfunction "C_10") (pintype "bidirectional"))
    )
    (net (code "145") (name "unconnected-(IC10-D-Pad9)") (class "Default")
      (node (ref "IC10") (pin "9") (pinfunction "D_9") (pintype "bidirectional"))
    )
    (net (code "146") (name "unconnected-(IC11-STRB-Pad1)") (class "Default")
      (node (ref "IC11") (pin "1") (pinfunction "STRB_1") (pintype "bidirectional"))
    )
    (net (code "147") (name "unconnected-(IC12-A-Pad15)") (class "Default")
      (node (ref "IC12") (pin "15") (pinfunction "A_15") (pintype "bidirectional"))
    )
    (net (code "148") (name "unconnected-(IC12-B-Pad1)") (class "Default")
      (node (ref "IC12") (pin "1") (pinfunction "B_1") (pintype "bidirectional"))
    )
    (net (code "149") (name "unconnected-(IC12-C-Pad10)") (class "Default")
      (node (ref "IC12") (pin "10") (pinfunction "C_10") (pintype "bidirectional"))
    )
    (net (code "150") (name "unconnected-(IC12-D-Pad9)") (class "Default")
      (node (ref "IC12") (pin "9") (pinfunction "D_9") (pintype "bidirectional"))
    )
    (net (code "151") (name "unconnected-(IC14-STRB-Pad1)") (class "Default")
      (node (ref "IC14") (pin "1") (pinfunction "STRB_1") (pintype "bidirectional"))
    )
    (net (code "152") (name "unconnected-(IC15-A-Pad15)") (class "Default")
      (node (ref "IC15") (pin "15") (pinfunction "A_15") (pintype "bidirectional"))
    )
    (net (code "153") (name "unconnected-(IC15-B-Pad1)") (class "Default")
      (node (ref "IC15") (pin "1") (pinfunction "B_1") (pintype "bidirectional"))
    )
    (net (code "154") (name "unconnected-(IC15-C-Pad10)") (class "Default")
      (node (ref "IC15") (pin "10") (pinfunction "C_10") (pintype "bidirectional"))
    )
    (net (code "155") (name "unconnected-(IC15-D-Pad9)") (class "Default")
      (node (ref "IC15") (pin "9") (pinfunction "D_9") (pintype "bidirectional"))
    )
    (net (code "156") (name "unconnected-(IC16-STRB-Pad1)") (class "Default")
      (node (ref "IC16") (pin "1") (pinfunction "STRB_1") (pintype "bidirectional"))
    )
    (net (code "157") (name "unconnected-(M_0X-DP-PadP$7)") (class "Default")
      (node (ref "M_0X") (pin "P$7") (pinfunction "DP_P$7") (pintype "passive"))
    )
    (net (code "158") (name "unconnected-(M_X0-DP-PadP$7)") (class "Default")
      (node (ref "M_X0") (pin "P$7") (pinfunction "DP_P$7") (pintype "passive"))
    )
    (net (code "159") (name "unconnected-(S_0X-DP-PadP$7)") (class "Default")
      (node (ref "S_0X") (pin "P$7") (pinfunction "DP_P$7") (pintype "passive"))
    )
    (net (code "160") (name "unconnected-(S_X0-DP-PadP$7)") (class "Default")
      (node (ref "S_X0") (pin "P$7") (pinfunction "DP_P$7") (pintype "passive"))
    )
    (net (code "161") (name "unconnected-(VR1-A-Pad1)") (class "Default")
      (node (ref "VR1") (pin "1") (pinfunction "A_1") (pintype "passive"))
    )
  )
)
